# isolation_verifier.net
KiCad netlist of a schematic drawn in Altium Designer
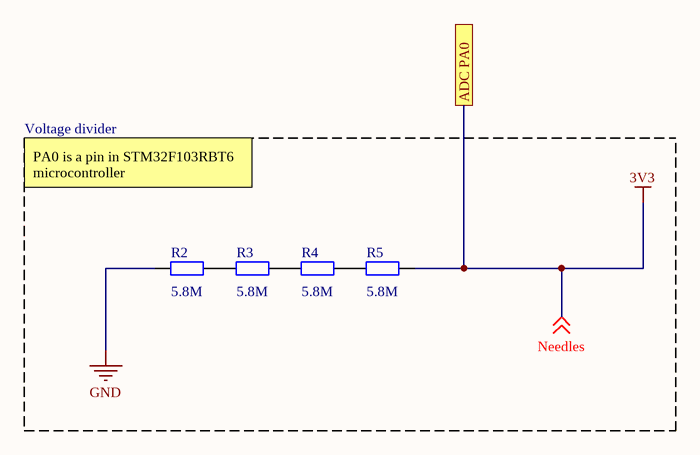
[diagram p0: isolation_verifier.SchDoc]

(export (version "E")
  (design (tool "Eeschema 10.0.6"))
  (components
    (comp (ref "R2")
      (value "5.8M")
      (footprint "AXIAL-0.4")
      (description "Resistor")
      (fields (field (name "Comment") "Res2") (field (name "PUBLISHER") "Altium Limited"))
      (libsource (lib "Miscellaneous Devices") (part "Res2"))
    )
    (comp (ref "R3")
      (value "5.8M")
      (footprint "AXIAL-0.4")
      (description "Resistor")
      (fields (field (name "Comment") "Res2") (field (name "PUBLISHER") "Altium Limited"))
      (libsource (lib "Miscellaneous Devices") (part "Res2"))
    )
    (comp (ref "R4")
      (value "5.8M")
      (footprint "AXIAL-0.4")
      (description "Resistor")
      (fields (field (name "Comment") "Res2") (field (name "PUBLISHER") "Altium Limited"))
      (libsource (lib "Miscellaneous Devices") (part "Res2"))
    )
    (comp (ref "R5")
      (value "5.8M")
      (footprint "AXIAL-0.4")
      (description "Resistor")
      (fields (field (name "Comment") "Res2") (field (name "PUBLISHER") "Altium Limited"))
      (libsource (lib "Miscellaneous Devices") (part "Res2"))
    )
  )
  (nets
    (net (code "1") (name "3V3") (class "Default")
      (node (ref "R5") (pin "2") (pinfunction "2_2") (pintype "passive"))
    )
    (net (code "2") (name "GND") (class "Default")
      (node (ref "R2") (pin "1") (pinfunction "1_1") (pintype "passive"))
    )
    (net (code "3") (name "Net-(R2-Pad2)") (class "Default")
      (node (ref "R2") (pin "2") (pinfunction "2_2") (pintype "passive"))
      (node (ref "R3") (pin "1") (pinfunction "1_1") (pintype "passive"))
    )
    (net (code "4") (name "Net-(R3-Pad2)") (class "Default")
      (node (ref "R3") (pin "2") (pinfunction "2_2") (pintype "passive"))
      (node (ref "R4") (pin "1") (pinfunction "1_1") (pintype "passive"))
    )
    (net (code "5") (name "Net-(R4-Pad2)") (class "Default")
      (node (ref "R4") (pin "2") (pinfunction "2_2") (pintype "passive"))
      (node (ref "R5") (pin "1") (pinfunction "1_1") (pintype "passive"))
    )
  )
)
